# Page2.net
KiCad netlist of a schematic drawn in Altium Designer
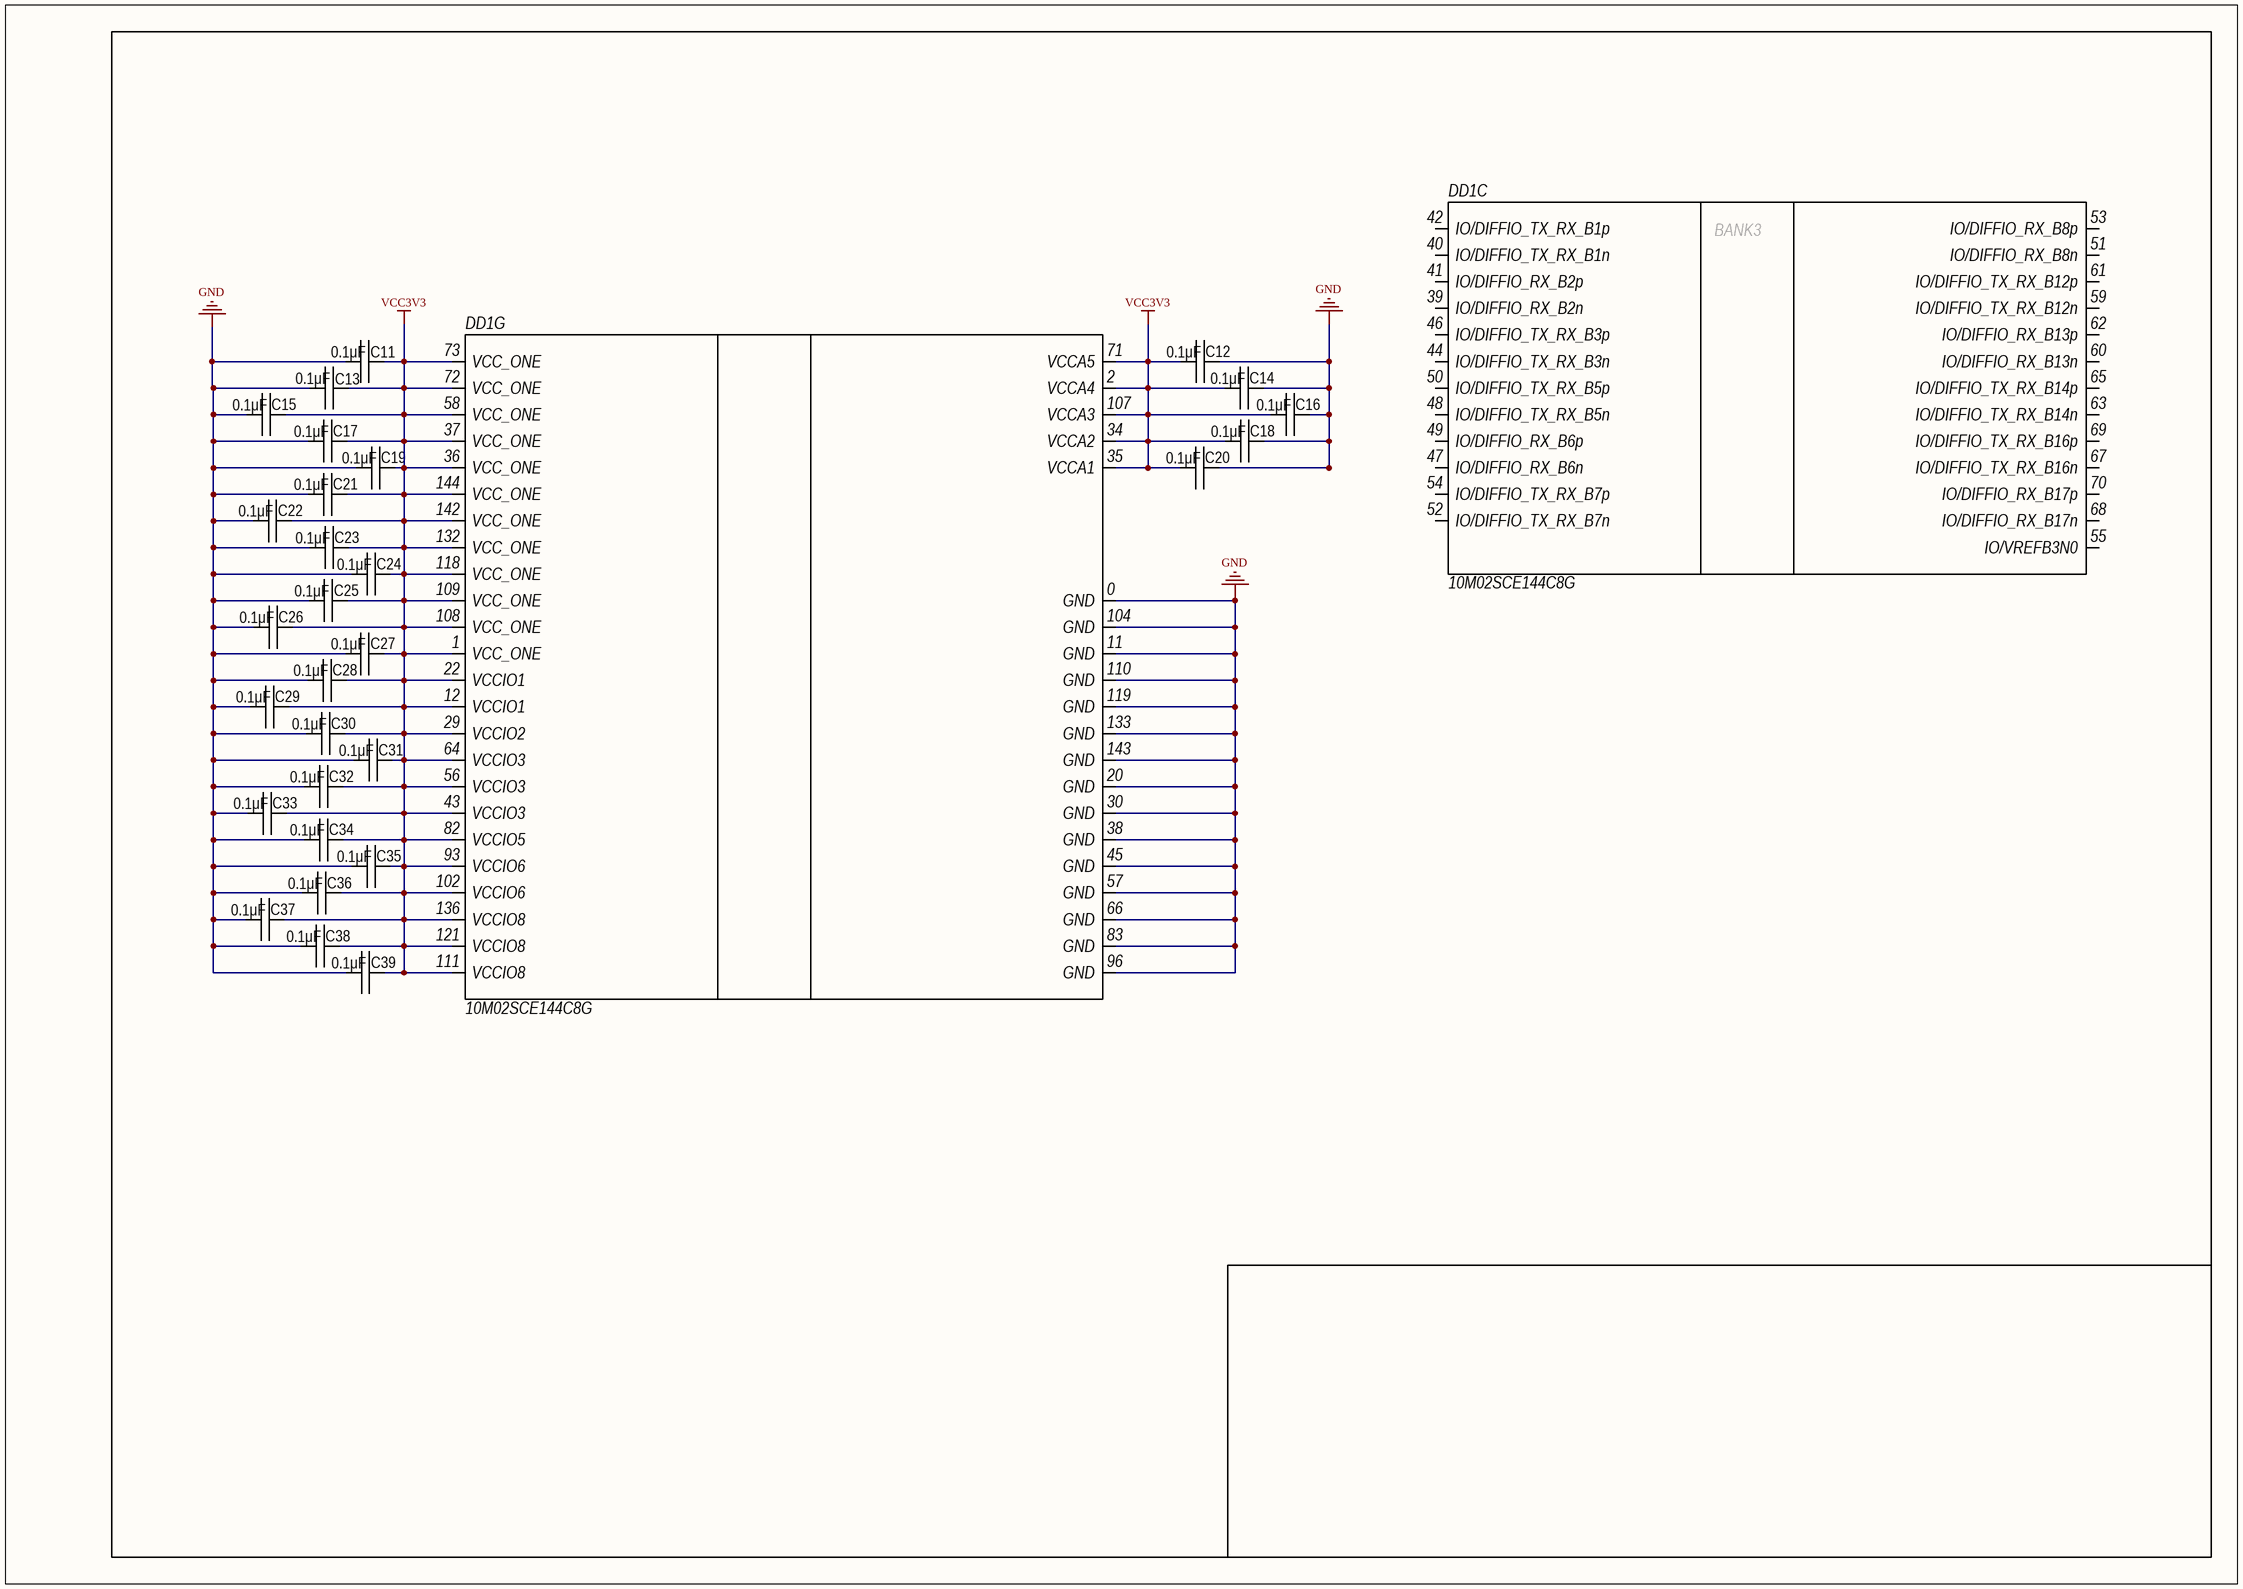
[diagram p0: Page2.SchDoc]

(export (version "E")
  (design (tool "Eeschema 10.0.6"))
  (components
    (comp (ref "C11")
      (value "0.1μF")
      (footprint "CAP: 0805")
      (fields (field (name "VALUEMANUFACTURERPARTNUMBER") "Ceramic capacitor, 0.1μF, X7R, , , 0805, "))
      (libsource (lib "Capacitor") (part "Ceramic_0805"))
    )
    (comp (ref "C12")
      (value "0.1μF")
      (footprint "CAP: 0805")
      (fields (field (name "VALUEMANUFACTURERPARTNUMBER") "Ceramic capacitor, 0.1μF, X7R, , , 0805, "))
      (libsource (lib "Capacitor") (part "Ceramic_0805"))
    )
    (comp (ref "C13")
      (value "0.1μF")
      (footprint "CAP: 0805")
      (fields (field (name "VALUEMANUFACTURERPARTNUMBER") "Ceramic capacitor, 0.1μF, X7R, , , 0805, "))
      (libsource (lib "Capacitor") (part "Ceramic_0805"))
    )
    (comp (ref "C14")
      (value "0.1μF")
      (footprint "CAP: 0805")
      (fields (field (name "VALUEMANUFACTURERPARTNUMBER") "Ceramic capacitor, 0.1μF, X7R, , , 0805, "))
      (libsource (lib "Capacitor") (part "Ceramic_0805"))
    )
    (comp (ref "C15")
      (value "0.1μF")
      (footprint "CAP: 0805")
      (fields (field (name "VALUEMANUFACTURERPARTNUMBER") "Ceramic capacitor, 0.1μF, X7R, , , 0805, "))
      (libsource (lib "Capacitor") (part "Ceramic_0805"))
    )
    (comp (ref "C16")
      (value "0.1μF")
      (footprint "CAP: 0805")
      (fields (field (name "VALUEMANUFACTURERPARTNUMBER") "Ceramic capacitor, 0.1μF, X7R, , , 0805, "))
      (libsource (lib "Capacitor") (part "Ceramic_0805"))
    )
    (comp (ref "C17")
      (value "0.1μF")
      (footprint "CAP: 0805")
      (fields (field (name "VALUEMANUFACTURERPARTNUMBER") "Ceramic capacitor, 0.1μF, X7R, , , 0805, "))
      (libsource (lib "Capacitor") (part "Ceramic_0805"))
    )
    (comp (ref "C18")
      (value "0.1μF")
      (footprint "CAP: 0805")
      (fields (field (name "VALUEMANUFACTURERPARTNUMBER") "Ceramic capacitor, 0.1μF, X7R, , , 0805, "))
      (libsource (lib "Capacitor") (part "Ceramic_0805"))
    )
    (comp (ref "C19")
      (value "0.1μF")
      (footprint "CAP: 0805")
      (fields (field (name "VALUEMANUFACTURERPARTNUMBER") "Ceramic capacitor, 0.1μF, X7R, , , 0805, "))
      (libsource (lib "Capacitor") (part "Ceramic_0805"))
    )
    (comp (ref "C20")
      (value "0.1μF")
      (footprint "CAP: 0805")
      (fields (field (name "VALUEMANUFACTURERPARTNUMBER") "Ceramic capacitor, 0.1μF, X7R, , , 0805, "))
      (libsource (lib "Capacitor") (part "Ceramic_0805"))
    )
    (comp (ref "C21")
      (value "0.1μF")
      (footprint "CAP: 0805")
      (fields (field (name "VALUEMANUFACTURERPARTNUMBER") "Ceramic capacitor, 0.1μF, X7R, , , 0805, "))
      (libsource (lib "Capacitor") (part "Ceramic_0805"))
    )
    (comp (ref "C22")
      (value "0.1μF")
      (footprint "CAP: 0805")
      (fields (field (name "VALUEMANUFACTURERPARTNUMBER") "Ceramic capacitor, 0.1μF, X7R, , , 0805, "))
      (libsource (lib "Capacitor") (part "Ceramic_0805"))
    )
    (comp (ref "C23")
      (value "0.1μF")
      (footprint "CAP: 0805")
      (fields (field (name "VALUEMANUFACTURERPARTNUMBER") "Ceramic capacitor, 0.1μF, X7R, , , 0805, "))
      (libsource (lib "Capacitor") (part "Ceramic_0805"))
    )
    (comp (ref "C24")
      (value "0.1μF")
      (footprint "CAP: 0805")
      (fields (field (name "VALUEMANUFACTURERPARTNUMBER") "Ceramic capacitor, 0.1μF, X7R, , , 0805, "))
      (libsource (lib "Capacitor") (part "Ceramic_0805"))
    )
    (comp (ref "C25")
      (value "0.1μF")
      (footprint "CAP: 0805")
      (fields (field (name "VALUEMANUFACTURERPARTNUMBER") "Ceramic capacitor, 0.1μF, X7R, , , 0805, "))
      (libsource (lib "Capacitor") (part "Ceramic_0805"))
    )
    (comp (ref "C26")
      (value "0.1μF")
      (footprint "CAP: 0805")
      (fields (field (name "VALUEMANUFACTURERPARTNUMBER") "Ceramic capacitor, 0.1μF, X7R, , , 0805, "))
      (libsource (lib "Capacitor") (part "Ceramic_0805"))
    )
    (comp (ref "C27")
      (value "0.1μF")
      (footprint "CAP: 0805")
      (fields (field (name "VALUEMANUFACTURERPARTNUMBER") "Ceramic capacitor, 0.1μF, X7R, , , 0805, "))
      (libsource (lib "Capacitor") (part "Ceramic_0805"))
    )
    (comp (ref "C28")
      (value "0.1μF")
      (footprint "CAP: 0805")
      (fields (field (name "VALUEMANUFACTURERPARTNUMBER") "Ceramic capacitor, 0.1μF, X7R, , , 0805, "))
      (libsource (lib "Capacitor") (part "Ceramic_0805"))
    )
    (comp (ref "C29")
      (value "0.1μF")
      (footprint "CAP: 0805")
      (fields (field (name "VALUEMANUFACTURERPARTNUMBER") "Ceramic capacitor, 0.1μF, X7R, , , 0805, "))
      (libsource (lib "Capacitor") (part "Ceramic_0805"))
    )
    (comp (ref "C30")
      (value "0.1μF")
      (footprint "CAP: 0805")
      (fields (field (name "VALUEMANUFACTURERPARTNUMBER") "Ceramic capacitor, 0.1μF, X7R, , , 0805, "))
      (libsource (lib "Capacitor") (part "Ceramic_0805"))
    )
    (comp (ref "C31")
      (value "0.1μF")
      (footprint "CAP: 0805")
      (fields (field (name "VALUEMANUFACTURERPARTNUMBER") "Ceramic capacitor, 0.1μF, X7R, , , 0805, "))
      (libsource (lib "Capacitor") (part "Ceramic_0805"))
    )
    (comp (ref "C32")
      (value "0.1μF")
      (footprint "CAP: 0805")
      (fields (field (name "VALUEMANUFACTURERPARTNUMBER") "Ceramic capacitor, 0.1μF, X7R, , , 0805, "))
      (libsource (lib "Capacitor") (part "Ceramic_0805"))
    )
    (comp (ref "C33")
      (value "0.1μF")
      (footprint "CAP: 0805")
      (fields (field (name "VALUEMANUFACTURERPARTNUMBER") "Ceramic capacitor, 0.1μF, X7R, , , 0805, "))
      (libsource (lib "Capacitor") (part "Ceramic_0805"))
    )
    (comp (ref "C34")
      (value "0.1μF")
      (footprint "CAP: 0805")
      (fields (field (name "VALUEMANUFACTURERPARTNUMBER") "Ceramic capacitor, 0.1μF, X7R, , , 0805, "))
      (libsource (lib "Capacitor") (part "Ceramic_0805"))
    )
    (comp (ref "C35")
      (value "0.1μF")
      (footprint "CAP: 0805")
      (fields (field (name "VALUEMANUFACTURERPARTNUMBER") "Ceramic capacitor, 0.1μF, X7R, , , 0805, "))
      (libsource (lib "Capacitor") (part "Ceramic_0805"))
    )
    (comp (ref "C36")
      (value "0.1μF")
      (footprint "CAP: 0805")
      (fields (field (name "VALUEMANUFACTURERPARTNUMBER") "Ceramic capacitor, 0.1μF, X7R, , , 0805, "))
      (libsource (lib "Capacitor") (part "Ceramic_0805"))
    )
    (comp (ref "C37")
      (value "0.1μF")
      (footprint "CAP: 0805")
      (fields (field (name "VALUEMANUFACTURERPARTNUMBER") "Ceramic capacitor, 0.1μF, X7R, , , 0805, "))
      (libsource (lib "Capacitor") (part "Ceramic_0805"))
    )
    (comp (ref "C38")
      (value "0.1μF")
      (footprint "CAP: 0805")
      (fields (field (name "VALUEMANUFACTURERPARTNUMBER") "Ceramic capacitor, 0.1μF, X7R, , , 0805, "))
      (libsource (lib "Capacitor") (part "Ceramic_0805"))
    )
    (comp (ref "C39")
      (value "0.1μF")
      (footprint "CAP: 0805")
      (fields (field (name "VALUEMANUFACTURERPARTNUMBER") "Ceramic capacitor, 0.1μF, X7R, , , 0805, "))
      (libsource (lib "Capacitor") (part "Ceramic_0805"))
    )
    (comp (ref "DD1")
      (value "10M02SCE144C8G")
      (footprint "144-Lead EQFP")
      (description "MAX10 FPGA")
      (fields (field (name "MANUFACTURER") "Intel"))
      (libsource (lib "Integrated_Library") (part "10M02SCE144C8G"))
    )
  )
  (nets
    (net (code "1") (name "GND") (class "Default")
      (node (ref "C11") (pin "2") (pinfunction "2_2") (pintype "power_in"))
      (node (ref "C12") (pin "1") (pinfunction "1_1") (pintype "power_in"))
      (node (ref "C13") (pin "2") (pinfunction "2_2") (pintype "power_in"))
      (node (ref "C14") (pin "1") (pinfunction "1_1") (pintype "power_in"))
      (node (ref "C15") (pin "2") (pinfunction "2_2") (pintype "power_in"))
      (node (ref "C16") (pin "1") (pinfunction "1_1") (pintype "power_in"))
      (node (ref "C17") (pin "2") (pinfunction "2_2") (pintype "power_in"))
      (node (ref "C18") (pin "1") (pinfunction "1_1") (pintype "power_in"))
      (node (ref "C19") (pin "2") (pinfunction "2_2") (pintype "power_in"))
      (node (ref "C20") (pin "1") (pinfunction "1_1") (pintype "power_in"))
      (node (ref "C21") (pin "2") (pinfunction "2_2") (pintype "power_in"))
      (node (ref "C22") (pin "2") (pinfunction "2_2") (pintype "power_in"))
      (node (ref "C23") (pin "2") (pinfunction "2_2") (pintype "power_in"))
      (node (ref "C24") (pin "2") (pinfunction "2_2") (pintype "power_in"))
      (node (ref "C25") (pin "2") (pinfunction "2_2") (pintype "power_in"))
      (node (ref "C26") (pin "2") (pinfunction "2_2") (pintype "power_in"))
      (node (ref "C27") (pin "2") (pinfunction "2_2") (pintype "power_in"))
      (node (ref "C28") (pin "2") (pinfunction "2_2") (pintype "power_in"))
      (node (ref "C29") (pin "2") (pinfunction "2_2") (pintype "power_in"))
      (node (ref "C30") (pin "2") (pinfunction "2_2") (pintype "power_in"))
      (node (ref "C31") (pin "2") (pinfunction "2_2") (pintype "power_in"))
      (node (ref "C32") (pin "2") (pinfunction "2_2") (pintype "power_in"))
      (node (ref "C33") (pin "2") (pinfunction "2_2") (pintype "power_in"))
      (node (ref "C34") (pin "2") (pinfunction "2_2") (pintype "power_in"))
      (node (ref "C35") (pin "2") (pinfunction "2_2") (pintype "power_in"))
      (node (ref "C36") (pin "2") (pinfunction "2_2") (pintype "power_in"))
      (node (ref "C37") (pin "2") (pinfunction "2_2") (pintype "power_in"))
      (node (ref "C38") (pin "2") (pinfunction "2_2") (pintype "power_in"))
      (node (ref "C39") (pin "2") (pinfunction "2_2") (pintype "power_in"))
      (node (ref "DD1") (pin "0") (pinfunction "GND_0") (pintype "power_in"))
      (node (ref "DD1") (pin "104") (pinfunction "GND_104") (pintype "power_in"))
      (node (ref "DD1") (pin "11") (pinfunction "GND_11") (pintype "power_in"))
      (node (ref "DD1") (pin "110") (pinfunction "GND_110") (pintype "power_in"))
      (node (ref "DD1") (pin "119") (pinfunction "GND_119") (pintype "power_in"))
      (node (ref "DD1") (pin "133") (pinfunction "GND_133") (pintype "power_in"))
      (node (ref "DD1") (pin "143") (pinfunction "GND_143") (pintype "power_in"))
      (node (ref "DD1") (pin "20") (pinfunction "GND_20") (pintype "power_in"))
      (node (ref "DD1") (pin "30") (pinfunction "GND_30") (pintype "power_in"))
      (node (ref "DD1") (pin "38") (pinfunction "GND_38") (pintype "power_in"))
      (node (ref "DD1") (pin "45") (pinfunction "GND_45") (pintype "power_in"))
      (node (ref "DD1") (pin "57") (pinfunction "GND_57") (pintype "power_in"))
      (node (ref "DD1") (pin "66") (pinfunction "GND_66") (pintype "power_in"))
      (node (ref "DD1") (pin "83") (pinfunction "GND_83") (pintype "power_in"))
      (node (ref "DD1") (pin "96") (pinfunction "GND_96") (pintype "power_in"))
    )
    (net (code "2") (name "VCC3V3") (class "Default")
      (node (ref "C11") (pin "1") (pinfunction "1_1") (pintype "power_in"))
      (node (ref "C12") (pin "2") (pinfunction "2_2") (pintype "power_in"))
      (node (ref "C13") (pin "1") (pinfunction "1_1") (pintype "power_in"))
      (node (ref "C14") (pin "2") (pinfunction "2_2") (pintype "power_in"))
      (node (ref "C15") (pin "1") (pinfunction "1_1") (pintype "power_in"))
      (node (ref "C16") (pin "2") (pinfunction "2_2") (pintype "power_in"))
      (node (ref "C17") (pin "1") (pinfunction "1_1") (pintype "power_in"))
      (node (ref "C18") (pin "2") (pinfunction "2_2") (pintype "power_in"))
      (node (ref "C19") (pin "1") (pinfunction "1_1") (pintype "power_in"))
      (node (ref "C20") (pin "2") (pinfunction "2_2") (pintype "power_in"))
      (node (ref "C21") (pin "1") (pinfunction "1_1") (pintype "power_in"))
      (node (ref "C22") (pin "1") (pinfunction "1_1") (pintype "power_in"))
      (node (ref "C23") (pin "1") (pinfunction "1_1") (pintype "power_in"))
      (node (ref "C24") (pin "1") (pinfunction "1_1") (pintype "power_in"))
      (node (ref "C25") (pin "1") (pinfunction "1_1") (pintype "power_in"))
      (node (ref "C26") (pin "1") (pinfunction "1_1") (pintype "power_in"))
      (node (ref "C27") (pin "1") (pinfunction "1_1") (pintype "power_in"))
      (node (ref "C28") (pin "1") (pinfunction "1_1") (pintype "power_in"))
      (node (ref "C29") (pin "1") (pinfunction "1_1") (pintype "power_in"))
      (node (ref "C30") (pin "1") (pinfunction "1_1") (pintype "power_in"))
      (node (ref "C31") (pin "1") (pinfunction "1_1") (pintype "power_in"))
      (node (ref "C32") (pin "1") (pinfunction "1_1") (pintype "power_in"))
      (node (ref "C33") (pin "1") (pinfunction "1_1") (pintype "power_in"))
      (node (ref "C34") (pin "1") (pinfunction "1_1") (pintype "power_in"))
      (node (ref "C35") (pin "1") (pinfunction "1_1") (pintype "power_in"))
      (node (ref "C36") (pin "1") (pinfunction "1_1") (pintype "power_in"))
      (node (ref "C37") (pin "1") (pinfunction "1_1") (pintype "power_in"))
      (node (ref "C38") (pin "1") (pinfunction "1_1") (pintype "power_in"))
      (node (ref "C39") (pin "1") (pinfunction "1_1") (pintype "power_in"))
      (node (ref "DD1") (pin "1") (pinfunction "VCC_ONE_1") (pintype "power_in"))
      (node (ref "DD1") (pin "102") (pinfunction "VCCIO6_102") (pintype "power_in"))
      (node (ref "DD1") (pin "107") (pinfunction "VCCA3_107") (pintype "power_in"))
      (node (ref "DD1") (pin "108") (pinfunction "VCC_ONE_108") (pintype "power_in"))
      (node (ref "DD1") (pin "109") (pinfunction "VCC_ONE_109") (pintype "power_in"))
      (node (ref "DD1") (pin "111") (pinfunction "VCCIO8_111") (pintype "power_in"))
      (node (ref "DD1") (pin "118") (pinfunction "VCC_ONE_118") (pintype "power_in"))
      (node (ref "DD1") (pin "12") (pinfunction "VCCIO1_12") (pintype "power_in"))
      (node (ref "DD1") (pin "121") (pinfunction "VCCIO8_121") (pintype "power_in"))
      (node (ref "DD1") (pin "132") (pinfunction "VCC_ONE_132") (pintype "power_in"))
      (node (ref "DD1") (pin "136") (pinfunction "VCCIO8_136") (pintype "power_in"))
      (node (ref "DD1") (pin "142") (pinfunction "VCC_ONE_142") (pintype "power_in"))
      (node (ref "DD1") (pin "144") (pinfunction "VCC_ONE_144") (pintype "power_in"))
      (node (ref "DD1") (pin "2") (pinfunction "VCCA4_2") (pintype "power_in"))
      (node (ref "DD1") (pin "22") (pinfunction "VCCIO1_22") (pintype "power_in"))
      (node (ref "DD1") (pin "29") (pinfunction "VCCIO2_29") (pintype "power_in"))
      (node (ref "DD1") (pin "34") (pinfunction "VCCA2_34") (pintype "power_in"))
      (node (ref "DD1") (pin "35") (pinfunction "VCCA1_35") (pintype "power_in"))
      (node (ref "DD1") (pin "36") (pinfunction "VCC_ONE_36") (pintype "power_in"))
      (node (ref "DD1") (pin "37") (pinfunction "VCC_ONE_37") (pintype "power_in"))
      (node (ref "DD1") (pin "43") (pinfunction "VCCIO3_43") (pintype "power_in"))
      (node (ref "DD1") (pin "56") (pinfunction "VCCIO3_56") (pintype "power_in"))
      (node (ref "DD1") (pin "58") (pinfunction "VCC_ONE_58") (pintype "power_in"))
      (node (ref "DD1") (pin "64") (pinfunction "VCCIO3_64") (pintype "power_in"))
      (node (ref "DD1") (pin "71") (pinfunction "VCCA5_71") (pintype "power_in"))
      (node (ref "DD1") (pin "72") (pinfunction "VCC_ONE_72") (pintype "power_in"))
      (node (ref "DD1") (pin "73") (pinfunction "VCC_ONE_73") (pintype "power_in"))
      (node (ref "DD1") (pin "82") (pinfunction "VCCIO5_82") (pintype "power_in"))
      (node (ref "DD1") (pin "93") (pinfunction "VCCIO6_93") (pintype "power_in"))
    )
    (net (code "3") (name "unconnected-(DD1C-IO{slash}DIFFIO_RX_B2n-Pad39)") (class "Default")
      (node (ref "DD1") (pin "39") (pinfunction "IO/DIFFIO_RX_B2n_39") (pintype "power_in"))
    )
    (net (code "4") (name "unconnected-(DD1C-IO{slash}DIFFIO_RX_B2p-Pad41)") (class "Default")
      (node (ref "DD1") (pin "41") (pinfunction "IO/DIFFIO_RX_B2p_41") (pintype "power_in"))
    )
    (net (code "5") (name "unconnected-(DD1C-IO{slash}DIFFIO_RX_B6n-Pad47)") (class "Default")
      (node (ref "DD1") (pin "47") (pinfunction "IO/DIFFIO_RX_B6n_47") (pintype "power_in"))
    )
    (net (code "6") (name "unconnected-(DD1C-IO{slash}DIFFIO_RX_B6p-Pad49)") (class "Default")
      (node (ref "DD1") (pin "49") (pinfunction "IO/DIFFIO_RX_B6p_49") (pintype "power_in"))
    )
    (net (code "7") (name "unconnected-(DD1C-IO{slash}DIFFIO_RX_B8n-Pad51)") (class "Default")
      (node (ref "DD1") (pin "51") (pinfunction "IO/DIFFIO_RX_B8n_51") (pintype "power_in"))
    )
    (net (code "8") (name "unconnected-(DD1C-IO{slash}DIFFIO_RX_B8p-Pad53)") (class "Default")
      (node (ref "DD1") (pin "53") (pinfunction "IO/DIFFIO_RX_B8p_53") (pintype "power_in"))
    )
    (net (code "9") (name "unconnected-(DD1C-IO{slash}DIFFIO_RX_B13n-Pad60)") (class "Default")
      (node (ref "DD1") (pin "60") (pinfunction "IO/DIFFIO_RX_B13n_60") (pintype "power_in"))
    )
    (net (code "10") (name "unconnected-(DD1C-IO{slash}DIFFIO_RX_B13p-Pad62)") (class "Default")
      (node (ref "DD1") (pin "62") (pinfunction "IO/DIFFIO_RX_B13p_62") (pintype "power_in"))
    )
    (net (code "11") (name "unconnected-(DD1C-IO{slash}DIFFIO_RX_B17n-Pad68)") (class "Default")
      (node (ref "DD1") (pin "68") (pinfunction "IO/DIFFIO_RX_B17n_68") (pintype "power_in"))
    )
    (net (code "12") (name "unconnected-(DD1C-IO{slash}DIFFIO_RX_B17p-Pad70)") (class "Default")
      (node (ref "DD1") (pin "70") (pinfunction "IO/DIFFIO_RX_B17p_70") (pintype "power_in"))
    )
    (net (code "13") (name "unconnected-(DD1C-IO{slash}DIFFIO_TX_RX_B1n-Pad40)") (class "Default")
      (node (ref "DD1") (pin "40") (pinfunction "IO/DIFFIO_TX_RX_B1n_40") (pintype "power_in"))
    )
    (net (code "14") (name "unconnected-(DD1C-IO{slash}DIFFIO_TX_RX_B1p-Pad42)") (class "Default")
      (node (ref "DD1") (pin "42") (pinfunction "IO/DIFFIO_TX_RX_B1p_42") (pintype "power_in"))
    )
    (net (code "15") (name "unconnected-(DD1C-IO{slash}DIFFIO_TX_RX_B3n-Pad44)") (class "Default")
      (node (ref "DD1") (pin "44") (pinfunction "IO/DIFFIO_TX_RX_B3n_44") (pintype "power_in"))
    )
    (net (code "16") (name "unconnected-(DD1C-IO{slash}DIFFIO_TX_RX_B3p-Pad46)") (class "Default")
      (node (ref "DD1") (pin "46") (pinfunction "IO/DIFFIO_TX_RX_B3p_46") (pintype "power_in"))
    )
    (net (code "17") (name "unconnected-(DD1C-IO{slash}DIFFIO_TX_RX_B5n-Pad48)") (class "Default")
      (node (ref "DD1") (pin "48") (pinfunction "IO/DIFFIO_TX_RX_B5n_48") (pintype "power_in"))
    )
    (net (code "18") (name "unconnected-(DD1C-IO{slash}DIFFIO_TX_RX_B5p-Pad50)") (class "Default")
      (node (ref "DD1") (pin "50") (pinfunction "IO/DIFFIO_TX_RX_B5p_50") (pintype "power_in"))
    )
    (net (code "19") (name "unconnected-(DD1C-IO{slash}DIFFIO_TX_RX_B7n-Pad52)") (class "Default")
      (node (ref "DD1") (pin "52") (pinfunction "IO/DIFFIO_TX_RX_B7n_52") (pintype "power_in"))
    )
    (net (code "20") (name "unconnected-(DD1C-IO{slash}DIFFIO_TX_RX_B7p-Pad54)") (class "Default")
      (node (ref "DD1") (pin "54") (pinfunction "IO/DIFFIO_TX_RX_B7p_54") (pintype "power_in"))
    )
    (net (code "21") (name "unconnected-(DD1C-IO{slash}DIFFIO_TX_RX_B12n-Pad59)") (class "Default")
      (node (ref "DD1") (pin "59") (pinfunction "IO/DIFFIO_TX_RX_B12n_59") (pintype "power_in"))
    )
    (net (code "22") (name "unconnected-(DD1C-IO{slash}DIFFIO_TX_RX_B12p-Pad61)") (class "Default")
      (node (ref "DD1") (pin "61") (pinfunction "IO/DIFFIO_TX_RX_B12p_61") (pintype "power_in"))
    )
    (net (code "23") (name "unconnected-(DD1C-IO{slash}DIFFIO_TX_RX_B14n-Pad63)") (class "Default")
      (node (ref "DD1") (pin "63") (pinfunction "IO/DIFFIO_TX_RX_B14n_63") (pintype "power_in"))
    )
    (net (code "24") (name "unconnected-(DD1C-IO{slash}DIFFIO_TX_RX_B14p-Pad65)") (class "Default")
      (node (ref "DD1") (pin "65") (pinfunction "IO/DIFFIO_TX_RX_B14p_65") (pintype "power_in"))
    )
    (net (code "25") (name "unconnected-(DD1C-IO{slash}DIFFIO_TX_RX_B16n-Pad67)") (class "Default")
      (node (ref "DD1") (pin "67") (pinfunction "IO/DIFFIO_TX_RX_B16n_67") (pintype "power_in"))
    )
    (net (code "26") (name "unconnected-(DD1C-IO{slash}DIFFIO_TX_RX_B16p-Pad69)") (class "Default")
      (node (ref "DD1") (pin "69") (pinfunction "IO/DIFFIO_TX_RX_B16p_69") (pintype "power_in"))
    )
    (net (code "27") (name "unconnected-(DD1C-IO{slash}VREFB3N0-Pad55)") (class "Default")
      (node (ref "DD1") (pin "55") (pinfunction "IO/VREFB3N0_55") (pintype "power_in"))
    )
  )
)
